# C64_Exp_cartridge.net
KiCad netlist of a schematic drawn in EAGLE
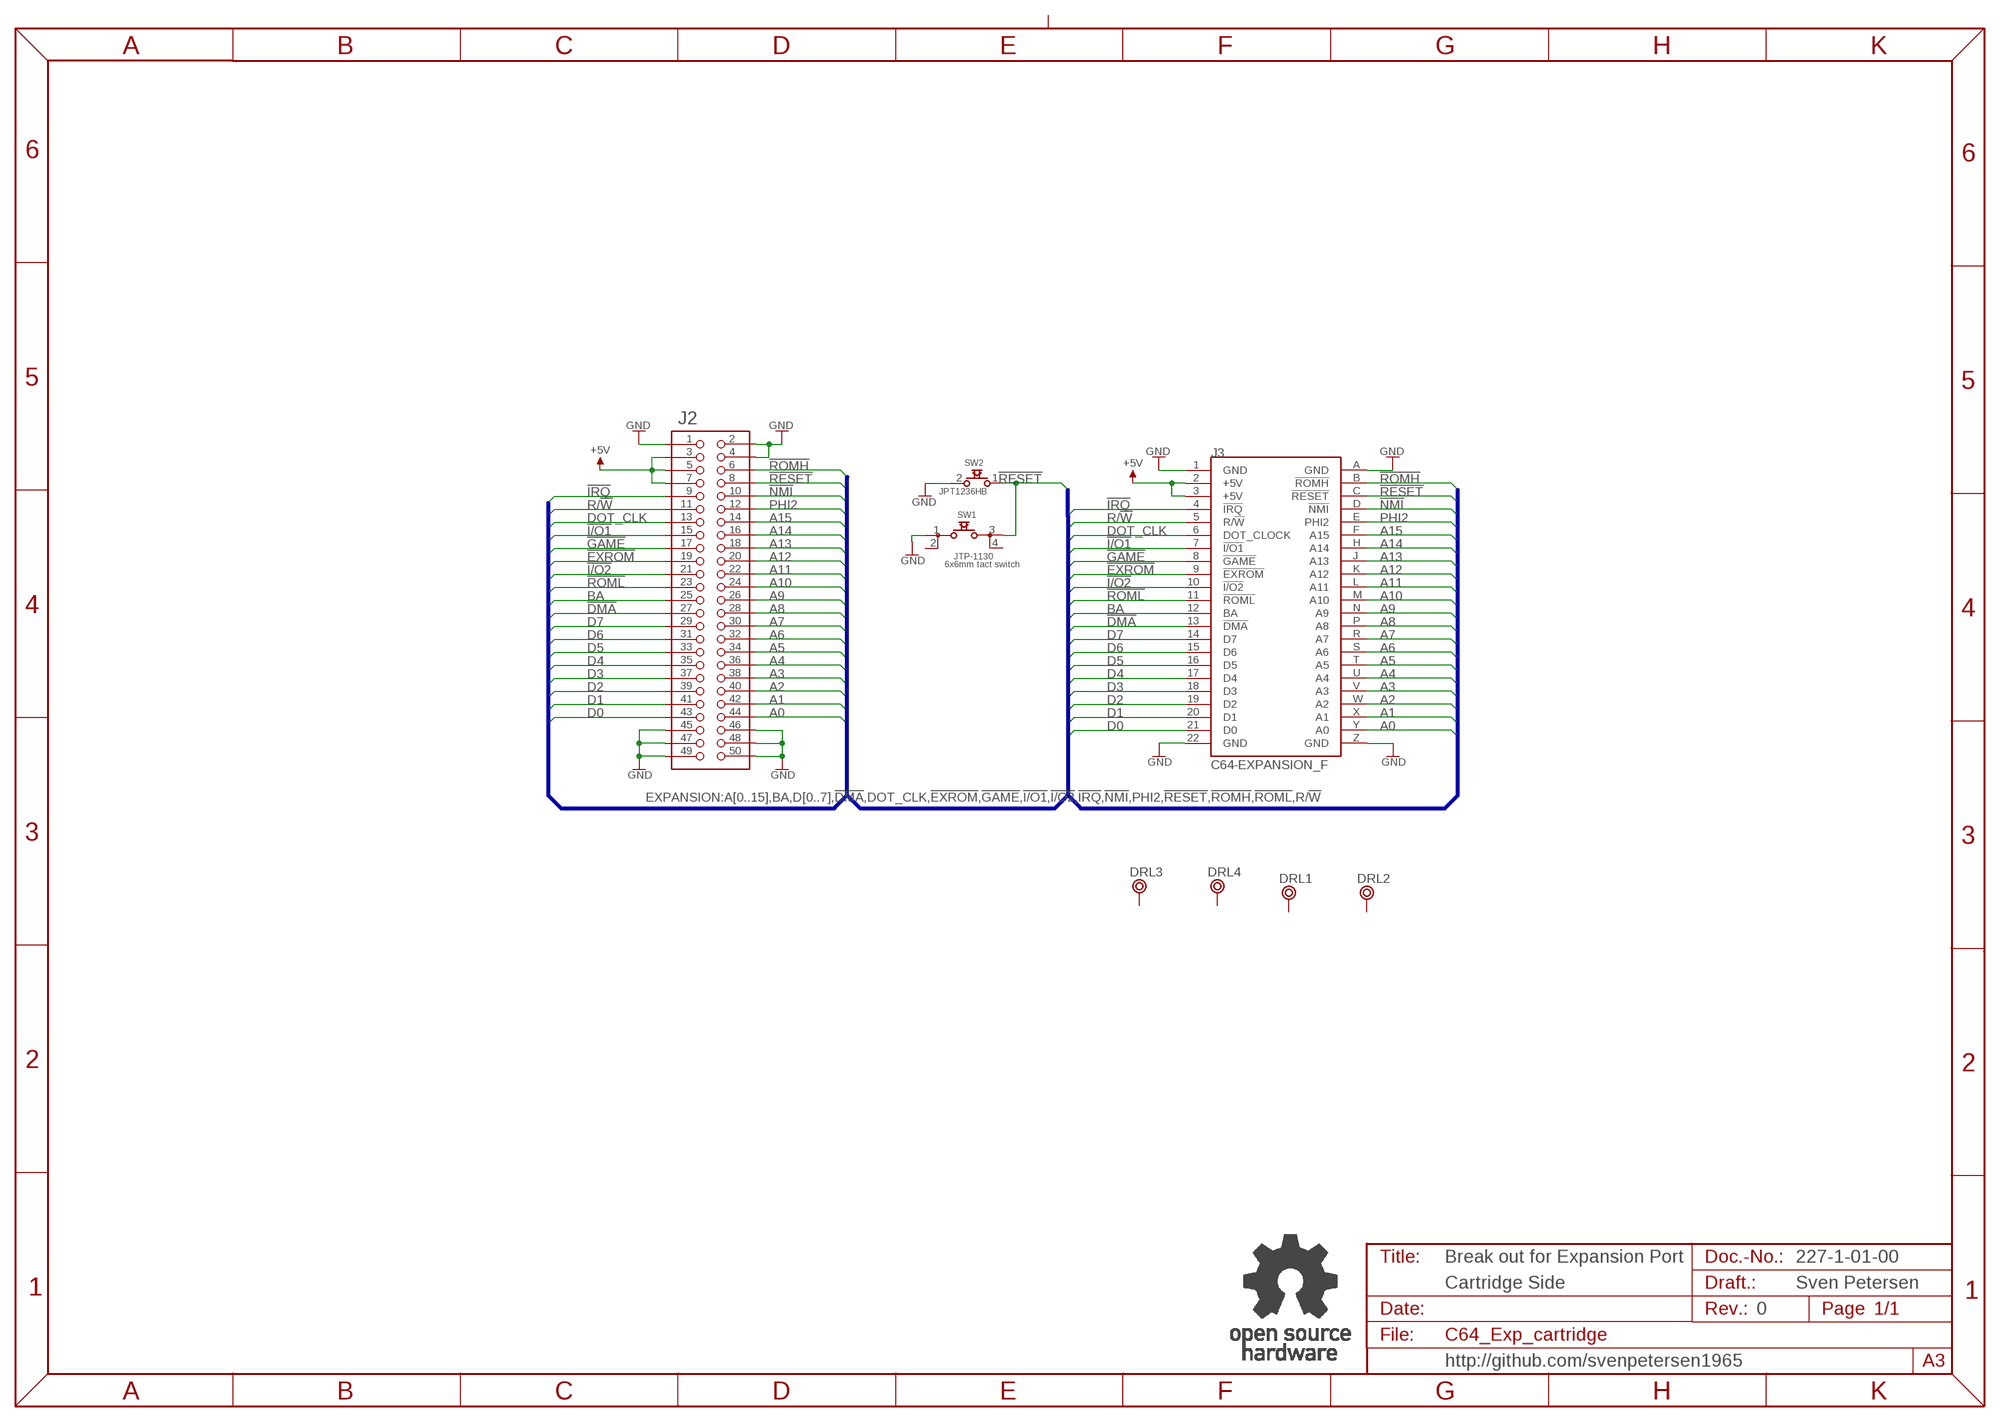
[diagram p0: schematic, sheet 1]

(export (version "E")
  (design (tool "Eeschema 10.0.6"))
  (components
    (comp (ref "DRL1")
      (value "BOHR3,3")
      (footprint "eagle-import:BOHR3,3")
      (libsource (lib "eagle-import") (part "BOHR3,3"))
    )
    (comp (ref "DRL2")
      (value "BOHR3,3")
      (footprint "eagle-import:BOHR3,3")
      (libsource (lib "eagle-import") (part "BOHR3,3"))
    )
    (comp (ref "DRL3")
      (value "BOHR3,3")
      (footprint "eagle-import:BOHR3,3")
      (libsource (lib "eagle-import") (part "BOHR3,3"))
    )
    (comp (ref "DRL4")
      (value "BOHR3,3")
      (footprint "eagle-import:BOHR3,3")
      (libsource (lib "eagle-import") (part "BOHR3,3"))
    )
    (comp (ref "J2")
      (value "PINHD-2X25BOX")
      (footprint "eagle-import:2X25WV")
      (libsource (lib "eagle-import") (part "PINHD-2X25BOX"))
    )
    (comp (ref "J3")
      (value "C64-EXPANSION_F")
      (footprint "eagle-import:EXPANSION_OUT")
      (libsource (lib "eagle-import") (part "C64-EXPANSION_F"))
    )
    (comp (ref "SW1")
      (value "JTP-1130")
      (footprint "eagle-import:JTP-1130")
      (libsource (lib "eagle-import") (part "JTP-1130"))
    )
    (comp (ref "SW2")
      (value "JPT1236HB")
      (footprint "eagle-import:JTP_1236HB")
      (libsource (lib "eagle-import") (part "JPT1236HB"))
    )
    (comp (ref "U$22")
      (value "OPEN_SOURCE_HW")
      (footprint "eagle-import:OPENHW")
      (libsource (lib "eagle-import") (part "OPEN_SOURCE_HW"))
    )
  )
  (nets
    (net (code "1") (name "+5V") (class "Default")
      (node (ref "J2") (pin "3") (pinfunction "3_3") (pintype "passive"))
      (node (ref "J2") (pin "5") (pinfunction "5_5") (pintype "passive"))
      (node (ref "J2") (pin "7") (pinfunction "7_7") (pintype "passive"))
      (node (ref "J3") (pin "2") (pinfunction "+5V_2") (pintype "power_in"))
      (node (ref "J3") (pin "3") (pinfunction "+5V_3") (pintype "power_in"))
    )
    (net (code "2") (name "/A0") (class "Default")
      (node (ref "J2") (pin "44") (pinfunction "44_44") (pintype "passive"))
      (node (ref "J3") (pin "Y") (pinfunction "A0_Y") (pintype "bidirectional"))
    )
    (net (code "3") (name "/A1") (class "Default")
      (node (ref "J2") (pin "42") (pinfunction "42_42") (pintype "passive"))
      (node (ref "J3") (pin "X") (pinfunction "A1_X") (pintype "bidirectional"))
    )
    (net (code "4") (name "/A2") (class "Default")
      (node (ref "J2") (pin "40") (pinfunction "40_40") (pintype "passive"))
      (node (ref "J3") (pin "W") (pinfunction "A2_W") (pintype "bidirectional"))
    )
    (net (code "5") (name "/A3") (class "Default")
      (node (ref "J2") (pin "38") (pinfunction "38_38") (pintype "passive"))
      (node (ref "J3") (pin "V") (pinfunction "A3_V") (pintype "bidirectional"))
    )
    (net (code "6") (name "/A4") (class "Default")
      (node (ref "J2") (pin "36") (pinfunction "36_36") (pintype "passive"))
      (node (ref "J3") (pin "U") (pinfunction "A4_U") (pintype "bidirectional"))
    )
    (net (code "7") (name "/A5") (class "Default")
      (node (ref "J2") (pin "34") (pinfunction "34_34") (pintype "passive"))
      (node (ref "J3") (pin "T") (pinfunction "A5_T") (pintype "bidirectional"))
    )
    (net (code "8") (name "/A6") (class "Default")
      (node (ref "J2") (pin "32") (pinfunction "32_32") (pintype "passive"))
      (node (ref "J3") (pin "S") (pinfunction "A6_S") (pintype "bidirectional"))
    )
    (net (code "9") (name "/A7") (class "Default")
      (node (ref "J2") (pin "30") (pinfunction "30_30") (pintype "passive"))
      (node (ref "J3") (pin "R") (pinfunction "A7_R") (pintype "bidirectional"))
    )
    (net (code "10") (name "/A8") (class "Default")
      (node (ref "J2") (pin "28") (pinfunction "28_28") (pintype "passive"))
      (node (ref "J3") (pin "P") (pinfunction "A8_P") (pintype "bidirectional"))
    )
    (net (code "11") (name "/A9") (class "Default")
      (node (ref "J2") (pin "26") (pinfunction "26_26") (pintype "passive"))
      (node (ref "J3") (pin "N") (pinfunction "A9_N") (pintype "bidirectional"))
    )
    (net (code "12") (name "/A10") (class "Default")
      (node (ref "J2") (pin "24") (pinfunction "24_24") (pintype "passive"))
      (node (ref "J3") (pin "M") (pinfunction "A10_M") (pintype "bidirectional"))
    )
    (net (code "13") (name "/A11") (class "Default")
      (node (ref "J2") (pin "22") (pinfunction "22_22") (pintype "passive"))
      (node (ref "J3") (pin "L") (pinfunction "A11_L") (pintype "bidirectional"))
    )
    (net (code "14") (name "/A12") (class "Default")
      (node (ref "J2") (pin "20") (pinfunction "20_20") (pintype "passive"))
      (node (ref "J3") (pin "K") (pinfunction "A12_K") (pintype "bidirectional"))
    )
    (net (code "15") (name "/A13") (class "Default")
      (node (ref "J2") (pin "18") (pinfunction "18_18") (pintype "passive"))
      (node (ref "J3") (pin "J") (pinfunction "A13_J") (pintype "bidirectional"))
    )
    (net (code "16") (name "/A14") (class "Default")
      (node (ref "J2") (pin "16") (pinfunction "16_16") (pintype "passive"))
      (node (ref "J3") (pin "H") (pinfunction "A14_H") (pintype "bidirectional"))
    )
    (net (code "17") (name "/A15") (class "Default")
      (node (ref "J2") (pin "14") (pinfunction "14_14") (pintype "passive"))
      (node (ref "J3") (pin "F") (pinfunction "A15_F") (pintype "bidirectional"))
    )
    (net (code "18") (name "/BA") (class "Default")
      (node (ref "J2") (pin "25") (pinfunction "25_25") (pintype "passive"))
      (node (ref "J3") (pin "12") (pinfunction "BA_12") (pintype "output"))
    )
    (net (code "19") (name "/D0") (class "Default")
      (node (ref "J2") (pin "43") (pinfunction "43_43") (pintype "passive"))
      (node (ref "J3") (pin "21") (pinfunction "D0_21") (pintype "bidirectional"))
    )
    (net (code "20") (name "/D1") (class "Default")
      (node (ref "J2") (pin "41") (pinfunction "41_41") (pintype "passive"))
      (node (ref "J3") (pin "20") (pinfunction "D1_20") (pintype "bidirectional"))
    )
    (net (code "21") (name "/D2") (class "Default")
      (node (ref "J2") (pin "39") (pinfunction "39_39") (pintype "passive"))
      (node (ref "J3") (pin "19") (pinfunction "D2_19") (pintype "bidirectional"))
    )
    (net (code "22") (name "/D3") (class "Default")
      (node (ref "J2") (pin "37") (pinfunction "37_37") (pintype "passive"))
      (node (ref "J3") (pin "18") (pinfunction "D3_18") (pintype "bidirectional"))
    )
    (net (code "23") (name "/D4") (class "Default")
      (node (ref "J2") (pin "35") (pinfunction "35_35") (pintype "passive"))
      (node (ref "J3") (pin "17") (pinfunction "D4_17") (pintype "bidirectional"))
    )
    (net (code "24") (name "/D5") (class "Default")
      (node (ref "J2") (pin "33") (pinfunction "33_33") (pintype "passive"))
      (node (ref "J3") (pin "16") (pinfunction "D5_16") (pintype "bidirectional"))
    )
    (net (code "25") (name "/D6") (class "Default")
      (node (ref "J2") (pin "31") (pinfunction "31_31") (pintype "passive"))
      (node (ref "J3") (pin "15") (pinfunction "D6_15") (pintype "bidirectional"))
    )
    (net (code "26") (name "/D7") (class "Default")
      (node (ref "J2") (pin "29") (pinfunction "29_29") (pintype "passive"))
      (node (ref "J3") (pin "14") (pinfunction "D7_14") (pintype "bidirectional"))
    )
    (net (code "27") (name "/DOT_CLK") (class "Default")
      (node (ref "J2") (pin "13") (pinfunction "13_13") (pintype "passive"))
      (node (ref "J3") (pin "6") (pinfunction "DOT_CLOCK_6") (pintype "output"))
    )
    (net (code "28") (name "/PHI2") (class "Default")
      (node (ref "J2") (pin "12") (pinfunction "12_12") (pintype "passive"))
      (node (ref "J3") (pin "E") (pinfunction "PHI2_E") (pintype "output"))
    )
    (net (code "29") (name "/R{slash}~{W}") (class "Default")
      (node (ref "J2") (pin "11") (pinfunction "11_11") (pintype "passive"))
      (node (ref "J3") (pin "5") (pinfunction "R/~{W}_5") (pintype "output"))
    )
    (net (code "31") (name "/~{DMA}") (class "Default")
      (node (ref "J2") (pin "27") (pinfunction "27_27") (pintype "passive"))
      (node (ref "J3") (pin "13") (pinfunction "~{DMA}_13") (pintype "input"))
    )
    (net (code "32") (name "/~{EXROM}") (class "Default")
      (node (ref "J2") (pin "19") (pinfunction "19_19") (pintype "passive"))
      (node (ref "J3") (pin "9") (pinfunction "~{EXROM}_9") (pintype "input"))
    )
    (net (code "33") (name "/~{GAME}") (class "Default")
      (node (ref "J2") (pin "17") (pinfunction "17_17") (pintype "passive"))
      (node (ref "J3") (pin "8") (pinfunction "~{GAME}_8") (pintype "input"))
    )
    (net (code "34") (name "/~{IRQ}") (class "Default")
      (node (ref "J2") (pin "9") (pinfunction "9_9") (pintype "passive"))
      (node (ref "J3") (pin "4") (pinfunction "~{IRQ}_4") (pintype "input"))
    )
    (net (code "35") (name "/~{I{slash}O1}") (class "Default")
      (node (ref "J2") (pin "15") (pinfunction "15_15") (pintype "passive"))
      (node (ref "J3") (pin "7") (pinfunction "~{I/O1}_7") (pintype "output"))
    )
    (net (code "36") (name "/~{I{slash}O2}") (class "Default")
      (node (ref "J2") (pin "21") (pinfunction "21_21") (pintype "passive"))
      (node (ref "J3") (pin "10") (pinfunction "~{I/O2}_10") (pintype "output"))
    )
    (net (code "37") (name "/~{NMI}") (class "Default")
      (node (ref "J2") (pin "10") (pinfunction "10_10") (pintype "passive"))
      (node (ref "J3") (pin "D") (pinfunction "~{NMI}_D") (pintype "input"))
    )
    (net (code "38") (name "/~{RESET}") (class "Default")
      (node (ref "J2") (pin "8") (pinfunction "8_8") (pintype "passive"))
      (node (ref "J3") (pin "C") (pinfunction "~{RESET}_C") (pintype "open_collector"))
      (node (ref "SW1") (pin "3") (pinfunction "3_3") (pintype "passive"))
      (node (ref "SW2") (pin "1") (pinfunction "1_1") (pintype "passive"))
    )
    (net (code "39") (name "/~{ROMH}") (class "Default")
      (node (ref "J2") (pin "6") (pinfunction "6_6") (pintype "passive"))
      (node (ref "J3") (pin "B") (pinfunction "~{ROMH}_B") (pintype "output"))
    )
    (net (code "40") (name "/~{ROML}") (class "Default")
      (node (ref "J2") (pin "23") (pinfunction "23_23") (pintype "passive"))
      (node (ref "J3") (pin "11") (pinfunction "~{ROML}_11") (pintype "output"))
    )
    (net (code "41") (name "GND") (class "Default")
      (node (ref "J2") (pin "1") (pinfunction "1_1") (pintype "passive"))
      (node (ref "J2") (pin "2") (pinfunction "2_2") (pintype "passive"))
      (node (ref "J2") (pin "4") (pinfunction "4_4") (pintype "passive"))
      (node (ref "J2") (pin "45") (pinfunction "45_45") (pintype "passive"))
      (node (ref "J2") (pin "46") (pinfunction "46_46") (pintype "passive"))
      (node (ref "J2") (pin "47") (pinfunction "47_47") (pintype "passive"))
      (node (ref "J2") (pin "48") (pinfunction "48_48") (pintype "passive"))
      (node (ref "J2") (pin "49") (pinfunction "49_49") (pintype "passive"))
      (node (ref "J2") (pin "50") (pinfunction "50_50") (pintype "passive"))
      (node (ref "J3") (pin "1") (pinfunction "GND_1") (pintype "power_in"))
      (node (ref "J3") (pin "22") (pinfunction "GND_22") (pintype "power_in"))
      (node (ref "J3") (pin "A") (pinfunction "GND_A") (pintype "power_in"))
      (node (ref "J3") (pin "Z") (pinfunction "GND_Z") (pintype "power_in"))
      (node (ref "SW1") (pin "1") (pinfunction "1_1") (pintype "passive"))
      (node (ref "SW2") (pin "2") (pinfunction "2_2") (pintype "passive"))
    )
    (net (code "42") (name "unconnected-(DRL1-PadP$1)") (class "Default")
      (node (ref "DRL1") (pin "P$1") (pinfunction "P$1_P$1") (pintype "passive"))
    )
    (net (code "43") (name "unconnected-(DRL2-PadP$1)") (class "Default")
      (node (ref "DRL2") (pin "P$1") (pinfunction "P$1_P$1") (pintype "passive"))
    )
    (net (code "44") (name "unconnected-(DRL3-PadP$1)") (class "Default")
      (node (ref "DRL3") (pin "P$1") (pinfunction "P$1_P$1") (pintype "passive"))
    )
    (net (code "45") (name "unconnected-(DRL4-PadP$1)") (class "Default")
      (node (ref "DRL4") (pin "P$1") (pinfunction "P$1_P$1") (pintype "passive"))
    )
    (net (code "46") (name "unconnected-(SW1-Pad2)") (class "Default")
      (node (ref "SW1") (pin "2") (pinfunction "2_2") (pintype "passive"))
    )
    (net (code "47") (name "unconnected-(SW1-Pad4)") (class "Default")
      (node (ref "SW1") (pin "4") (pinfunction "4_4") (pintype "passive"))
    )
  )
)
